# ios.net
KiCad netlist of a schematic drawn in Altium Designer
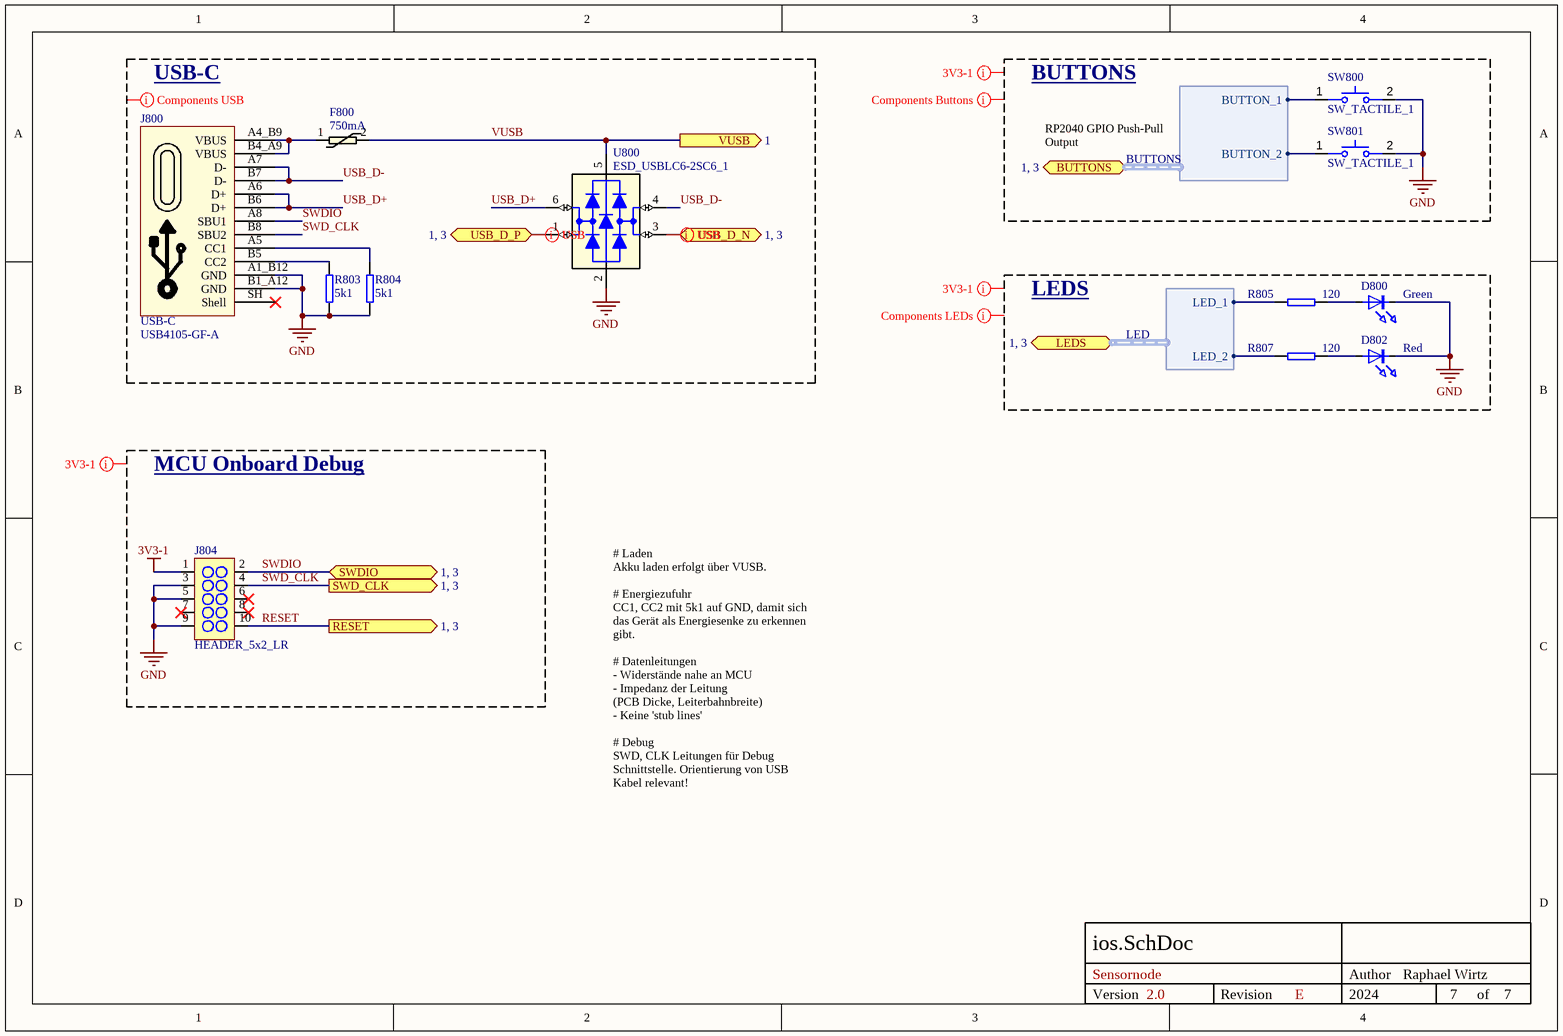
[diagram p0: ios.SchDoc]

(export (version "E")
  (design (tool "Eeschema 10.0.6"))
  (components
    (comp (ref "D800")
      (value "Green")
      (footprint "sensornode:0603-Diode")
      (libsource (lib "sensornode_v2") (part "LED_1"))
    )
    (comp (ref "D802")
      (value "Red")
      (footprint "sensornode:0603-Diode")
      (libsource (lib "sensornode_v2") (part "LED_1"))
    )
    (comp (ref "F800")
      (value "750mA")
      (footprint "sensornode:1206")
      (description "Resettable Fuse")
      (libsource (lib "sensornode_v2") (part "FUSE_1"))
    )
    (comp (ref "J800")
      (value "USB-C")
      (footprint "sensornode:USB_GCT_4105-GF-A")
      (description "Connector 24 (16+8 Dummy)")
      (fields (field (name "ALTIUM_VALUE") "USB4105-GF-A"))
      (libsource (lib "sensornode_v2") (part "USB-C_2"))
    )
    (comp (ref "J804")
      (value "HEADER_5x2_LR")
      (footprint "sensornode:HEADER_SMD_1.27")
      (libsource (lib "sensornode_v2") (part "HEADER_5x2_LR"))
    )
    (comp (ref "R803")
      (value "5k1")
      (footprint "sensornode:0603")
      (description "Normaler Widerstand")
      (libsource (lib "sensornode_v2") (part "R?"))
    )
    (comp (ref "R804")
      (value "5k1")
      (footprint "sensornode:0603")
      (description "Normaler Widerstand")
      (libsource (lib "sensornode_v2") (part "R?"))
    )
    (comp (ref "R805")
      (value "120")
      (footprint "sensornode:0603")
      (description "Normaler Widerstand")
      (libsource (lib "sensornode_v2") (part "R?"))
    )
    (comp (ref "R807")
      (value "120")
      (footprint "sensornode:0603")
      (description "Normaler Widerstand")
      (libsource (lib "sensornode_v2") (part "R?"))
    )
    (comp (ref "SW800")
      (value "SW_TACTILE_1")
      (footprint "sensornode:SWITCH_B3FS1010P")
      (libsource (lib "sensornode_v2") (part "SW_TACTILE_1"))
    )
    (comp (ref "SW801")
      (value "SW_TACTILE_1")
      (footprint "sensornode:SWITCH_B3FS1010P")
      (libsource (lib "sensornode_v2") (part "SW_TACTILE_1"))
    )
    (comp (ref "U800")
      (value "ESD_USBLC6-2SC6_1")
      (footprint "sensornode:SOT95P280X145-6N")
      (description "17V Clamp 5A (8/20Âµs) Ipp Tvs Diode Surface Mount SOT-23-6")
      (fields (field (name "MF") "STMicroelectronics") (field (name "MP") "USBLC6-2SC6"))
      (libsource (lib "sensornode_v2") (part "ESD_USBLC6-2SC6_1"))
    )
  )
  (nets
    (net (code "3") (name "/BUTTON_1") (class "Default")
      (node (ref "SW800") (pin "1") (pinfunction "1_1") (pintype "passive"))
    )
    (net (code "4") (name "/BUTTON_2") (class "Default")
      (node (ref "SW801") (pin "1") (pinfunction "1_1") (pintype "passive"))
    )
    (net (code "5") (name "/LED_1") (class "Default") (node (ref "R805") (pin "2") (pintype "passive")))
    (net (code "6") (name "/LED_2") (class "Default") (node (ref "R807") (pin "2") (pintype "passive")))
    (net (code "7") (name "/RESET") (class "Default")
      (node (ref "J804") (pin "10") (pinfunction "10_10") (pintype "passive"))
    )
    (net (code "8") (name "/SWDIO") (class "Default")
      (node (ref "J800") (pin "A8") (pinfunction "SBU1_A8") (pintype "passive"))
      (node (ref "J804") (pin "2") (pinfunction "2_2") (pintype "passive"))
    )
    (net (code "9") (name "/SWD_CLK") (class "Default")
      (node (ref "J800") (pin "B8") (pinfunction "SBU2_B8") (pintype "passive"))
      (node (ref "J804") (pin "4") (pinfunction "4_4") (pintype "passive"))
    )
    (net (code "10") (name "/USB_D+") (class "Default")
      (node (ref "J800") (pin "A6") (pinfunction "D+_A6") (pintype "passive"))
      (node (ref "J800") (pin "B6") (pinfunction "D+_B6") (pintype "passive"))
      (node (ref "U800") (pin "6") (pinfunction "I/O1_OUT_6") (pintype "bidirectional"))
    )
    (net (code "11") (name "/USB_D-") (class "Default")
      (node (ref "J800") (pin "A7") (pinfunction "D-_A7") (pintype "passive"))
      (node (ref "J800") (pin "B7") (pinfunction "D-_B7") (pintype "passive"))
      (node (ref "U800") (pin "4") (pinfunction "I/O2_OUT_4") (pintype "bidirectional"))
    )
    (net (code "12") (name "/USB_D_N") (class "Default")
      (node (ref "U800") (pin "3") (pinfunction "I/O2_IN_3") (pintype "bidirectional"))
    )
    (net (code "13") (name "/USB_D_P") (class "Default")
      (node (ref "U800") (pin "1") (pinfunction "I/O1_IN_1") (pintype "bidirectional"))
    )
    (net (code "14") (name "/VUSB") (class "Default")
      (node (ref "F800") (pin "2") (pinfunction "2_2") (pintype "passive"))
      (node (ref "U800") (pin "5") (pinfunction "VBUS_5") (pintype "power_in"))
    )
    (net (code "17") (name "3V3-1") (class "Default")
      (node (ref "J804") (pin "1") (pinfunction "1_1") (pintype "passive"))
    )
    (net (code "18") (name "GND") (class "Default")
      (node (ref "D800") (pin "K") (pinfunction "K_K") (pintype "passive"))
      (node (ref "D802") (pin "K") (pinfunction "K_K") (pintype "passive"))
      (node (ref "J800") (pin "A1_B12") (pinfunction "GND_A1_B12") (pintype "passive"))
      (node (ref "J800") (pin "B1_A12") (pinfunction "GND_B1_A12") (pintype "passive"))
      (node (ref "J804") (pin "3") (pinfunction "3_3") (pintype "passive"))
      (node (ref "J804") (pin "5") (pinfunction "5_5") (pintype "passive"))
      (node (ref "J804") (pin "9") (pinfunction "9_9") (pintype "passive"))
      (node (ref "R803") (pin "1") (pintype "passive"))
      (node (ref "R804") (pin "1") (pintype "passive"))
      (node (ref "SW800") (pin "2") (pinfunction "2_2") (pintype "passive"))
      (node (ref "SW801") (pin "2") (pinfunction "2_2") (pintype "passive"))
      (node (ref "U800") (pin "2") (pinfunction "GND_2") (pintype "power_in"))
    )
    (net (code "19") (name "Net-(D800-PadA)") (class "Default")
      (node (ref "D800") (pin "A") (pinfunction "A_A") (pintype "passive"))
      (node (ref "R805") (pin "1") (pintype "passive"))
    )
    (net (code "20") (name "Net-(D802-PadA)") (class "Default")
      (node (ref "D802") (pin "A") (pinfunction "A_A") (pintype "passive"))
      (node (ref "R807") (pin "1") (pintype "passive"))
    )
    (net (code "21") (name "Net-(F800-Pad1)") (class "Default")
      (node (ref "F800") (pin "1") (pinfunction "1_1") (pintype "passive"))
      (node (ref "J800") (pin "A4_B9") (pinfunction "VBUS_A4_B9") (pintype "passive"))
      (node (ref "J800") (pin "B4_A9") (pinfunction "VBUS_B4_A9") (pintype "passive"))
    )
    (net (code "22") (name "Net-(J800-CC1)") (class "Default")
      (node (ref "J800") (pin "A5") (pinfunction "CC1_A5") (pintype "passive"))
      (node (ref "R804") (pin "2") (pintype "passive"))
    )
    (net (code "23") (name "Net-(J800-CC2)") (class "Default")
      (node (ref "J800") (pin "B5") (pinfunction "CC2_B5") (pintype "passive"))
      (node (ref "R803") (pin "2") (pintype "passive"))
    )
    (net (code "24") (name "unconnected-(J800-Shell-PadSH)") (class "Default")
      (node (ref "J800") (pin "SH") (pinfunction "Shell_SH") (pintype "passive+no_connect"))
    )
    (net (code "25") (name "unconnected-(J804-Pad6)") (class "Default")
      (node (ref "J804") (pin "6") (pinfunction "6_6") (pintype "passive+no_connect"))
    )
    (net (code "26") (name "unconnected-(J804-Pad7)") (class "Default")
      (node (ref "J804") (pin "7") (pinfunction "7_7") (pintype "passive+no_connect"))
    )
    (net (code "27") (name "unconnected-(J804-Pad8)") (class "Default")
      (node (ref "J804") (pin "8") (pinfunction "8_8") (pintype "passive+no_connect"))
    )
  )
)
